# esp_pilote_clean.net
KiCad netlist of a schematic drawn in EAGLE
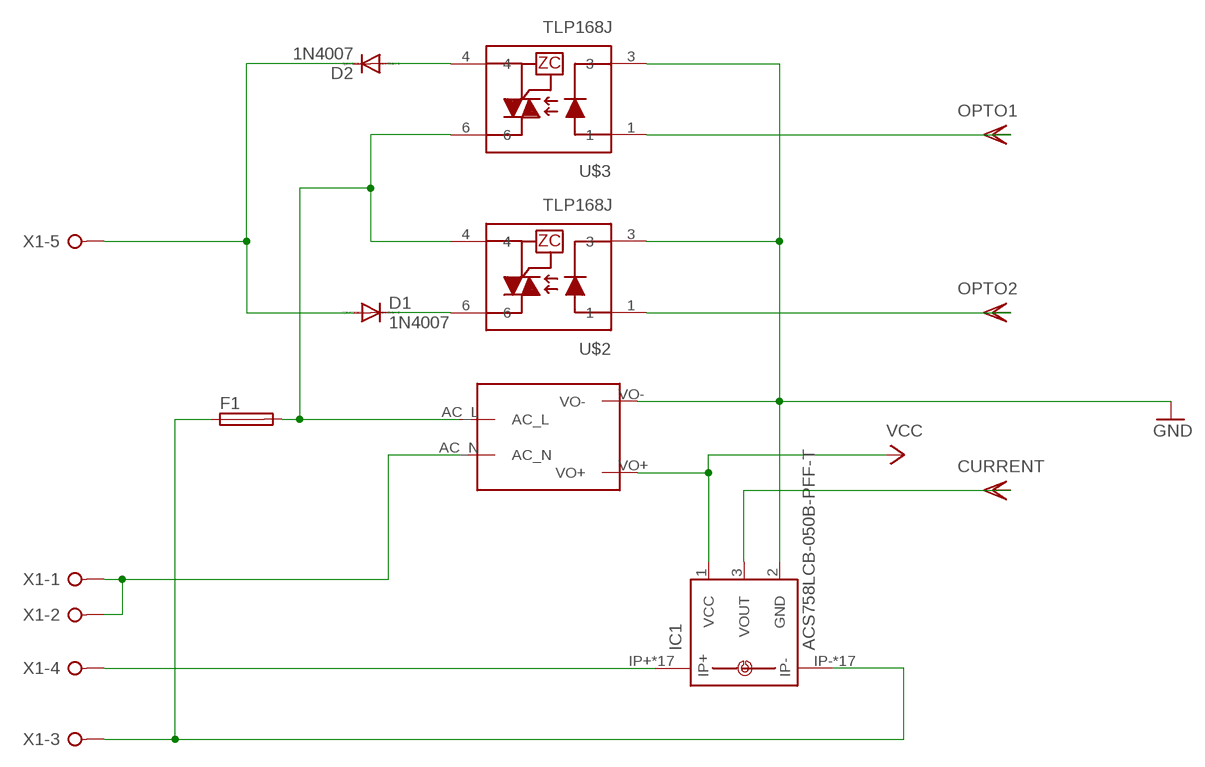
[diagram p0: schematic, sheet 1]
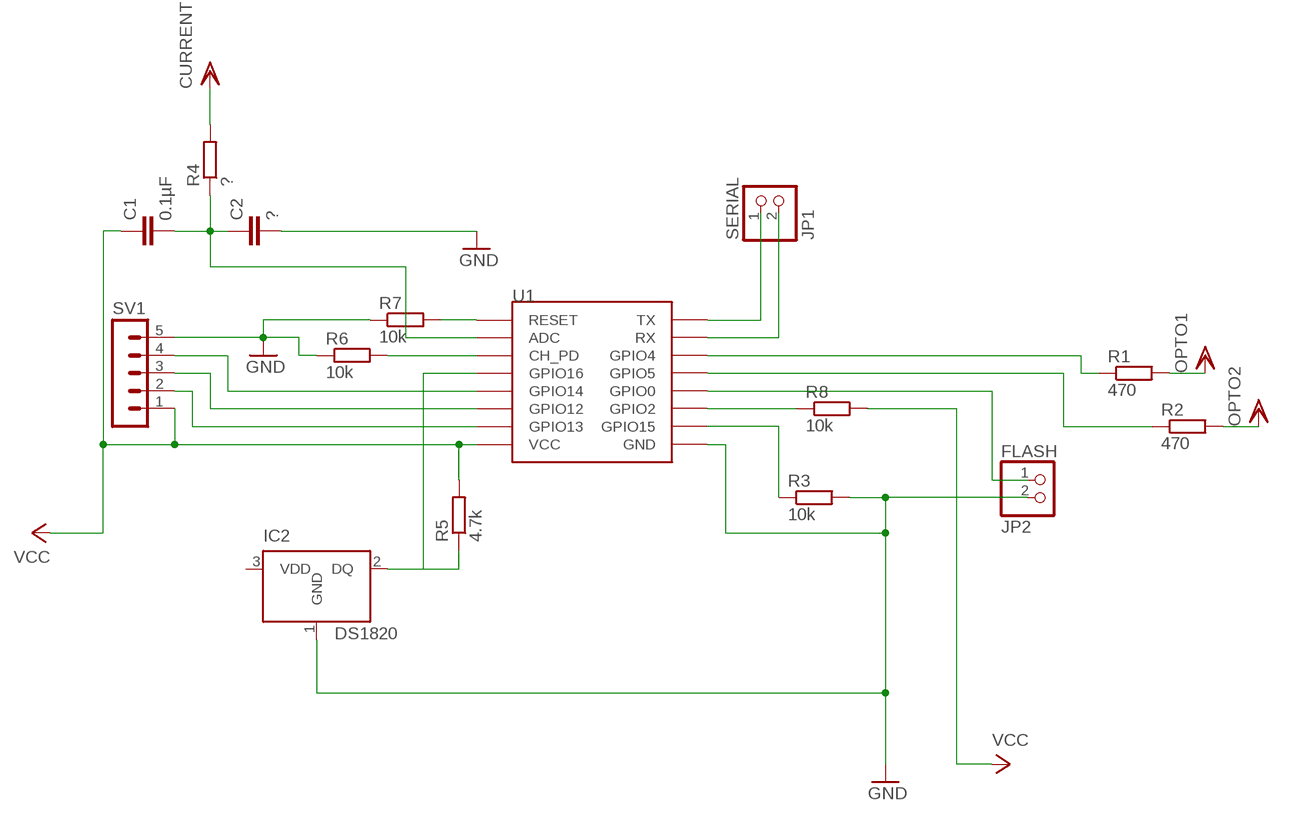
[diagram p1: schematic, sheet 2]

(export (version "E")
  (design (tool "Eeschema 10.0.6"))
  (components
    (comp (ref "D1")
      (value "1N4007")
      (footprint "eagle-import:DO41-10")
      (libsource (lib "eagle-import") (part "1N4004"))
    )
    (comp (ref "D2")
      (value "1N4007")
      (footprint "eagle-import:DO41-10")
      (libsource (lib "eagle-import") (part "1N4004"))
    )
    (comp (ref "F1")
      (value "19560")
      (footprint "eagle-import:19560")
      (fields (field (name "MPN") "56000001009"))
      (libsource (lib "eagle-import") (part "19560"))
    )
    (comp (ref "IC1")
      (value "ACS758LCB-050B-PFF-T")
      (footprint "eagle-import:CB-PFF")
      (libsource (lib "eagle-import") (part "ACS758LCB-050B-PFF-T"))
    )
    (comp (ref "U$1")
      (value "MAINS_CONVERTERS")
      (footprint "eagle-import:HLK-PM01")
      (libsource (lib "eagle-import") (part "MAINS_CONVERTERS"))
    )
    (comp (ref "U$2")
      (value "TLP168J")
      (footprint "eagle-import:MFSOP-4")
      (libsource (lib "eagle-import") (part "TLP168J"))
    )
    (comp (ref "U$3")
      (value "TLP168J")
      (footprint "eagle-import:MFSOP-4")
      (libsource (lib "eagle-import") (part "TLP168J"))
    )
    (comp (ref "X1")
      (value "W237-05P")
      (footprint "eagle-import:W237-5P")
      (libsource (lib "eagle-import") (part "W237-05P"))
    )
    (comp (ref "C1")
      (value "0.1µF")
      (footprint "eagle-import:C5B3.5")
      (libsource (lib "eagle-import") (part "C5/3.5"))
    )
    (comp (ref "C2")
      (value "?")
      (footprint "eagle-import:C5B3.5")
      (libsource (lib "eagle-import") (part "C5/3.5"))
    )
    (comp (ref "FLASH")
      (value "JP2")
      (footprint "eagle-import:1X02")
      (libsource (lib "eagle-import") (part "PINHD-1X2"))
    )
    (comp (ref "IC2")
      (value "DS1820")
      (footprint "eagle-import:TO-92")
      (libsource (lib "eagle-import") (part "DS1820"))
    )
    (comp (ref "R1")
      (value "470")
      (footprint "eagle-import:0207_10")
      (libsource (lib "eagle-import") (part "R-EU_0207/10"))
    )
    (comp (ref "R2")
      (value "470")
      (footprint "eagle-import:0207_10")
      (libsource (lib "eagle-import") (part "R-EU_0207/10"))
    )
    (comp (ref "R3")
      (value "10k")
      (footprint "eagle-import:0207_10")
      (libsource (lib "eagle-import") (part "R-EU_0207/10"))
    )
    (comp (ref "R4")
      (value "?")
      (footprint "eagle-import:0207_10")
      (libsource (lib "eagle-import") (part "R-EU_0207/10"))
    )
    (comp (ref "R5")
      (value "4.7k")
      (footprint "eagle-import:0207_10")
      (libsource (lib "eagle-import") (part "R-EU_0207/10"))
    )
    (comp (ref "R6")
      (value "10k")
      (footprint "eagle-import:0207_10")
      (libsource (lib "eagle-import") (part "R-EU_0207/10"))
    )
    (comp (ref "R7")
      (value "10k")
      (footprint "eagle-import:0207_10")
      (libsource (lib "eagle-import") (part "R-EU_0207/10"))
    )
    (comp (ref "R8")
      (value "10k")
      (footprint "eagle-import:0207_10")
      (libsource (lib "eagle-import") (part "R-EU_0207/10"))
    )
    (comp (ref "SERIAL")
      (value "JP1")
      (footprint "eagle-import:1X02")
      (libsource (lib "eagle-import") (part "PINHD-1X2"))
    )
    (comp (ref "SV1")
      (value "MA05-1")
      (footprint "eagle-import:MA05-1")
      (libsource (lib "eagle-import") (part "MA05-1"))
    )
    (comp (ref "U1")
      (value "ESP12SMD")
      (footprint "eagle-import:ESP12-SMD")
      (libsource (lib "eagle-import") (part "ESP12SMD"))
    )
  )
  (nets
    (net (code "1") (name "CURENT") (class "Default")
      (node (ref "IC1") (pin "3") (pinfunction "VOUT_3") (pintype "output"))
      (node (ref "R4") (pin "2") (pinfunction "2_2") (pintype "passive"))
    )
    (net (code "2") (name "GND") (class "Default")
      (node (ref "C2") (pin "2") (pinfunction "2_2") (pintype "passive"))
      (node (ref "FLASH") (pin "2") (pinfunction "2_2") (pintype "passive"))
      (node (ref "IC1") (pin "2") (pinfunction "GND_2") (pintype "power_in"))
      (node (ref "IC2") (pin "1") (pinfunction "GND_1") (pintype "power_in"))
      (node (ref "R3") (pin "2") (pinfunction "2_2") (pintype "passive"))
      (node (ref "R6") (pin "1") (pinfunction "1_1") (pintype "passive"))
      (node (ref "R7") (pin "1") (pinfunction "1_1") (pintype "passive"))
      (node (ref "SV1") (pin "5") (pinfunction "5_5") (pintype "passive"))
      (node (ref "U$1") (pin "VO-") (pinfunction "VO-_VO-") (pintype "output"))
      (node (ref "U$2") (pin "3") (pinfunction "3_3") (pintype "bidirectional"))
      (node (ref "U$3") (pin "3") (pinfunction "3_3") (pintype "bidirectional"))
      (node (ref "U1") (pin "GND") (pinfunction "GND_GND") (pintype "bidirectional"))
    )
    (net (code "3") (name "Net-(C1-Pad2)") (class "Default")
      (node (ref "C1") (pin "2") (pinfunction "2_2") (pintype "passive"))
      (node (ref "C2") (pin "1") (pinfunction "1_1") (pintype "passive"))
      (node (ref "R4") (pin "1") (pinfunction "1_1") (pintype "passive"))
      (node (ref "U1") (pin "ADC") (pinfunction "ADC_ADC") (pintype "bidirectional"))
    )
    (net (code "4") (name "Net-(D1-PadC)") (class "Default")
      (node (ref "D1") (pin "C") (pinfunction "C_C") (pintype "passive"))
      (node (ref "U$2") (pin "6") (pinfunction "6_6") (pintype "bidirectional"))
    )
    (net (code "5") (name "Net-(D2-PadA)") (class "Default")
      (node (ref "D2") (pin "A") (pinfunction "A_A") (pintype "passive"))
      (node (ref "U$3") (pin "4") (pinfunction "4_4") (pintype "bidirectional"))
    )
    (net (code "6") (name "Net-(F1-Pad2)") (class "Default")
      (node (ref "F1") (pin "2") (pinfunction "2_2") (pintype "passive"))
      (node (ref "U$1") (pin "AC_L") (pinfunction "AC_L_AC_L") (pintype "input"))
      (node (ref "U$2") (pin "4") (pinfunction "4_4") (pintype "bidirectional"))
      (node (ref "U$3") (pin "6") (pinfunction "6_6") (pintype "bidirectional"))
    )
    (net (code "7") (name "Net-(FLASH-Pad1)") (class "Default")
      (node (ref "FLASH") (pin "1") (pinfunction "1_1") (pintype "passive"))
      (node (ref "U1") (pin "GPIO0") (pinfunction "GPIO0_GPIO0") (pintype "bidirectional"))
    )
    (net (code "8") (name "Net-(IC2-DQ)") (class "Default")
      (node (ref "IC2") (pin "2") (pinfunction "DQ_2") (pintype "output"))
      (node (ref "R5") (pin "1") (pinfunction "1_1") (pintype "passive"))
      (node (ref "U1") (pin "GPIO16") (pinfunction "GPIO16_GPIO16") (pintype "bidirectional"))
    )
    (net (code "9") (name "Net-(R1-Pad1)") (class "Default")
      (node (ref "R1") (pin "1") (pinfunction "1_1") (pintype "passive"))
      (node (ref "U1") (pin "GPIO4") (pinfunction "GPIO4_GPIO4") (pintype "bidirectional"))
    )
    (net (code "10") (name "Net-(R2-Pad1)") (class "Default")
      (node (ref "R2") (pin "1") (pinfunction "1_1") (pintype "passive"))
      (node (ref "U1") (pin "GPIO5") (pinfunction "GPIO5_GPIO5") (pintype "bidirectional"))
    )
    (net (code "11") (name "Net-(R3-Pad1)") (class "Default")
      (node (ref "R3") (pin "1") (pinfunction "1_1") (pintype "passive"))
      (node (ref "U1") (pin "GPIO15") (pinfunction "GPIO15_GPIO15") (pintype "bidirectional"))
    )
    (net (code "12") (name "Net-(R6-Pad2)") (class "Default")
      (node (ref "R6") (pin "2") (pinfunction "2_2") (pintype "passive"))
      (node (ref "U1") (pin "CH_PD") (pinfunction "CH_PD_CH_PD") (pintype "bidirectional"))
    )
    (net (code "13") (name "Net-(R7-Pad2)") (class "Default")
      (node (ref "R7") (pin "2") (pinfunction "2_2") (pintype "passive"))
      (node (ref "U1") (pin "RESET") (pinfunction "RESET_RESET") (pintype "bidirectional"))
    )
    (net (code "14") (name "Net-(R8-Pad1)") (class "Default")
      (node (ref "R8") (pin "1") (pinfunction "1_1") (pintype "passive"))
      (node (ref "U1") (pin "GPIO2") (pinfunction "GPIO2_GPIO2") (pintype "bidirectional"))
    )
    (net (code "15") (name "Net-(SV1-Pad2)") (class "Default")
      (node (ref "SV1") (pin "2") (pinfunction "2_2") (pintype "passive"))
      (node (ref "U1") (pin "GPIO13") (pinfunction "GPIO13_GPIO13") (pintype "bidirectional"))
    )
    (net (code "16") (name "Net-(SV1-Pad3)") (class "Default")
      (node (ref "SV1") (pin "3") (pinfunction "3_3") (pintype "passive"))
      (node (ref "U1") (pin "GPIO12") (pinfunction "GPIO12_GPIO12") (pintype "bidirectional"))
    )
    (net (code "17") (name "Net-(SV1-Pad4)") (class "Default")
      (node (ref "SV1") (pin "4") (pinfunction "4_4") (pintype "passive"))
      (node (ref "U1") (pin "GPIO14") (pinfunction "GPIO14_GPIO14") (pintype "bidirectional"))
    )
    (net (code "18") (name "Net-(U1-RX)") (class "Default")
      (node (ref "SERIAL") (pin "2") (pinfunction "2_2") (pintype "passive"))
      (node (ref "U1") (pin "RXD0") (pinfunction "RX_RXD0") (pintype "bidirectional"))
    )
    (net (code "19") (name "Net-(U1-TX)") (class "Default")
      (node (ref "SERIAL") (pin "1") (pinfunction "1_1") (pintype "passive"))
      (node (ref "U1") (pin "TXD0") (pinfunction "TX_TXD0") (pintype "bidirectional"))
    )
    (net (code "20") (name "Net-(X1A-KL)") (class "Default")
      (node (ref "U$1") (pin "AC_N") (pinfunction "AC_N_AC_N") (pintype "input"))
      (node (ref "X1") (pin "1") (pinfunction "KL_1") (pintype "passive"))
      (node (ref "X1") (pin "2") (pinfunction "KL_2") (pintype "passive"))
    )
    (net (code "21") (name "Net-(X1C-KL)") (class "Default")
      (node (ref "F1") (pin "1") (pinfunction "1_1") (pintype "passive"))
      (node (ref "IC1") (pin "IP-") (pinfunction "IP-_IP-") (pintype "passive"))
      (node (ref "IC1") (pin "IP-@10") (pinfunction "IP-_IP-@10") (pintype "passive"))
      (node (ref "IC1") (pin "IP-@11") (pinfunction "IP-_IP-@11") (pintype "passive"))
      (node (ref "IC1") (pin "IP-@12") (pinfunction "IP-_IP-@12") (pintype "passive"))
      (node (ref "IC1") (pin "IP-@13") (pinfunction "IP-_IP-@13") (pintype "passive"))
      (node (ref "IC1") (pin "IP-@14") (pinfunction "IP-_IP-@14") (pintype "passive"))
      (node (ref "IC1") (pin "IP-@15") (pinfunction "IP-_IP-@15") (pintype "passive"))
      (node (ref "IC1") (pin "IP-@16") (pinfunction "IP-_IP-@16") (pintype "passive"))
      (node (ref "IC1") (pin "IP-@17") (pinfunction "IP-_IP-@17") (pintype "passive"))
      (node (ref "IC1") (pin "IP-@2") (pinfunction "IP-_IP-@2") (pintype "passive"))
      (node (ref "IC1") (pin "IP-@3") (pinfunction "IP-_IP-@3") (pintype "passive"))
      (node (ref "IC1") (pin "IP-@4") (pinfunction "IP-_IP-@4") (pintype "passive"))
      (node (ref "IC1") (pin "IP-@5") (pinfunction "IP-_IP-@5") (pintype "passive"))
      (node (ref "IC1") (pin "IP-@6") (pinfunction "IP-_IP-@6") (pintype "passive"))
      (node (ref "IC1") (pin "IP-@7") (pinfunction "IP-_IP-@7") (pintype "passive"))
      (node (ref "IC1") (pin "IP-@8") (pinfunction "IP-_IP-@8") (pintype "passive"))
      (node (ref "IC1") (pin "IP-@9") (pinfunction "IP-_IP-@9") (pintype "passive"))
      (node (ref "X1") (pin "3") (pinfunction "KL_3") (pintype "passive"))
    )
    (net (code "22") (name "Net-(X1D-KL)") (class "Default")
      (node (ref "IC1") (pin "IP+") (pinfunction "IP+_IP+") (pintype "passive"))
      (node (ref "IC1") (pin "IP+@10") (pinfunction "IP+_IP+@10") (pintype "passive"))
      (node (ref "IC1") (pin "IP+@11") (pinfunction "IP+_IP+@11") (pintype "passive"))
      (node (ref "IC1") (pin "IP+@12") (pinfunction "IP+_IP+@12") (pintype "passive"))
      (node (ref "IC1") (pin "IP+@13") (pinfunction "IP+_IP+@13") (pintype "passive"))
      (node (ref "IC1") (pin "IP+@14") (pinfunction "IP+_IP+@14") (pintype "passive"))
      (node (ref "IC1") (pin "IP+@15") (pinfunction "IP+_IP+@15") (pintype "passive"))
      (node (ref "IC1") (pin "IP+@16") (pinfunction "IP+_IP+@16") (pintype "passive"))
      (node (ref "IC1") (pin "IP+@17") (pinfunction "IP+_IP+@17") (pintype "passive"))
      (node (ref "IC1") (pin "IP+@2") (pinfunction "IP+_IP+@2") (pintype "passive"))
      (node (ref "IC1") (pin "IP+@3") (pinfunction "IP+_IP+@3") (pintype "passive"))
      (node (ref "IC1") (pin "IP+@4") (pinfunction "IP+_IP+@4") (pintype "passive"))
      (node (ref "IC1") (pin "IP+@5") (pinfunction "IP+_IP+@5") (pintype "passive"))
      (node (ref "IC1") (pin "IP+@6") (pinfunction "IP+_IP+@6") (pintype "passive"))
      (node (ref "IC1") (pin "IP+@7") (pinfunction "IP+_IP+@7") (pintype "passive"))
      (node (ref "IC1") (pin "IP+@8") (pinfunction "IP+_IP+@8") (pintype "passive"))
      (node (ref "IC1") (pin "IP+@9") (pinfunction "IP+_IP+@9") (pintype "passive"))
      (node (ref "X1") (pin "4") (pinfunction "KL_4") (pintype "passive"))
    )
    (net (code "23") (name "Net-(X1E-KL)") (class "Default")
      (node (ref "D1") (pin "A") (pinfunction "A_A") (pintype "passive"))
      (node (ref "D2") (pin "C") (pinfunction "C_C") (pintype "passive"))
      (node (ref "X1") (pin "5") (pinfunction "KL_5") (pintype "passive"))
    )
    (net (code "24") (name "OPTO1") (class "Default")
      (node (ref "R1") (pin "2") (pinfunction "2_2") (pintype "passive"))
      (node (ref "U$3") (pin "1") (pinfunction "1_1") (pintype "bidirectional"))
    )
    (net (code "25") (name "OPTO2") (class "Default")
      (node (ref "R2") (pin "2") (pinfunction "2_2") (pintype "passive"))
      (node (ref "U$2") (pin "1") (pinfunction "1_1") (pintype "bidirectional"))
    )
    (net (code "26") (name "VCC") (class "Default")
      (node (ref "C1") (pin "1") (pinfunction "1_1") (pintype "passive"))
      (node (ref "IC1") (pin "1") (pinfunction "VCC_1") (pintype "power_in"))
      (node (ref "R5") (pin "2") (pinfunction "2_2") (pintype "passive"))
      (node (ref "R8") (pin "2") (pinfunction "2_2") (pintype "passive"))
      (node (ref "SV1") (pin "1") (pinfunction "1_1") (pintype "passive"))
      (node (ref "U$1") (pin "VO+") (pinfunction "VO+_VO+") (pintype "output"))
      (node (ref "U1") (pin "VCC") (pinfunction "VCC_VCC") (pintype "bidirectional"))
    )
    (net (code "27") (name "unconnected-(IC2-VDD-Pad3)") (class "Default")
      (node (ref "IC2") (pin "3") (pinfunction "VDD_3") (pintype "input"))
    )
  )
)
